# USB.net
KiCad netlist of a schematic drawn in Altium Designer
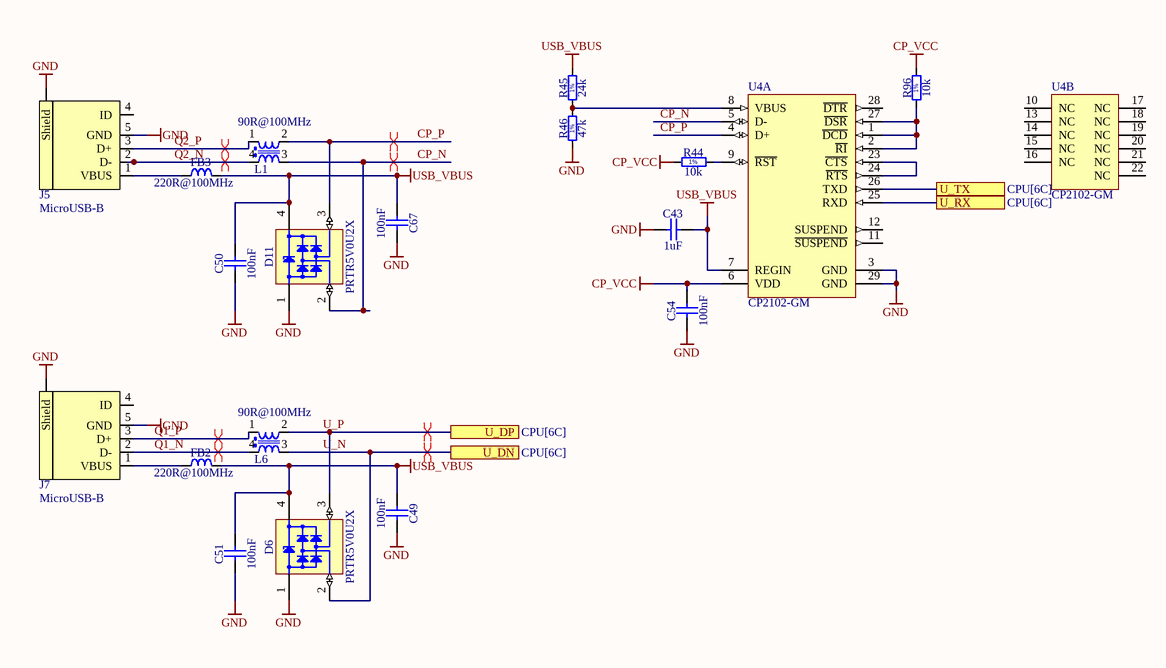
[diagram p0: USB.SchDoc]

(export (version "E")
  (design (tool "Eeschema 10.0.6"))
  (components
    (comp (ref "C43")
      (value "1uF")
      (footprint "CAPC1005X55N")
      (description "Non-polarised capacitor")
      (fields
        (field (name "PART NUMBER") "CC0402_1UF_16V_10%_X5R")
        (field (name "VOLTAGE") "16V")
        (field (name "AUTHOR") "CERN DEM JLC")
      )
      (libsource (lib "Capacitors") (part "Capacitor - non polarized"))
    )
    (comp (ref "C49")
      (value "100nF")
      (footprint "CAPC1005X55N")
      (description "Non-polarised capacitor")
      (fields
        (field (name "PART NUMBER") "CC0402_100NF_16V_10%_X5R")
        (field (name "VOLTAGE") "16V")
        (field (name "AUTHOR") "CERN DEM JLC")
      )
      (libsource (lib "Capacitors") (part "Capacitor - non polarized"))
    )
    (comp (ref "C50")
      (value "100nF")
      (footprint "CAPC1005X55N")
      (description "Non-polarised capacitor")
      (fields
        (field (name "PART NUMBER") "CC0402_100NF_16V_10%_X5R")
        (field (name "VOLTAGE") "16V")
        (field (name "AUTHOR") "CERN DEM JLC")
      )
      (libsource (lib "Capacitors") (part "Capacitor - non polarized"))
    )
    (comp (ref "C51")
      (value "100nF")
      (footprint "CAPC1005X55N")
      (description "Non-polarised capacitor")
      (fields
        (field (name "PART NUMBER") "CC0402_100NF_16V_10%_X5R")
        (field (name "VOLTAGE") "16V")
        (field (name "AUTHOR") "CERN DEM JLC")
      )
      (libsource (lib "Capacitors") (part "Capacitor - non polarized"))
    )
    (comp (ref "C54")
      (value "100nF")
      (footprint "CAPC1005X55N")
      (description "Non-polarised capacitor")
      (fields
        (field (name "PART NUMBER") "CC0402_100NF_16V_10%_X5R")
        (field (name "VOLTAGE") "16V")
        (field (name "AUTHOR") "CERN DEM JLC")
      )
      (libsource (lib "Capacitors") (part "Capacitor - non polarized"))
    )
    (comp (ref "C67")
      (value "100nF")
      (footprint "CAPC1005X55N")
      (description "Non-polarised capacitor")
      (fields
        (field (name "PART NUMBER") "CC0402_100NF_16V_10%_X5R")
        (field (name "VOLTAGE") "16V")
        (field (name "AUTHOR") "CERN DEM JLC")
      )
      (libsource (lib "Capacitors") (part "Capacitor - non polarized"))
    )
    (comp (ref "D6")
      (value "PRTR5V0U2X")
      (footprint "SOT190P230X110-4N")
      (description "Ultra Low Capacitance Double Rail-to-Rail ESD Protection Diode")
      (fields
        (field (name "VOLTAGE") "5.5V")
        (field (name "MANUFACTURER") "NXP SEMICONDUCTORS")
        (field (name "AUTHOR") "CERN DEM JLC")
      )
      (libsource (lib "ICs And Semiconductors") (part "PRTR5V0U2X"))
    )
    (comp (ref "D11")
      (value "PRTR5V0U2X")
      (footprint "SOT190P230X110-4N")
      (description "Ultra Low Capacitance Double Rail-to-Rail ESD Protection Diode")
      (fields
        (field (name "VOLTAGE") "5.5V")
        (field (name "MANUFACTURER") "NXP SEMICONDUCTORS")
        (field (name "AUTHOR") "CERN DEM JLC")
      )
      (libsource (lib "ICs And Semiconductors") (part "PRTR5V0U2X"))
    )
    (comp (ref "FB2")
      (value "220R@100MHz")
      (footprint "INDC2012X105N")
      (description "Inductor")
      (fields
        (field (name "PART NUMBER") "IND0805_MURATA_BLM21PG221SN1D")
        (field (name "POWER") "2A")
        (field (name "AUTHOR") "CERN DEM JLC")
      )
      (libsource (lib "Inductors & Transformers") (part "Inductor"))
    )
    (comp (ref "FB3")
      (value "220R@100MHz")
      (footprint "INDC2012X105N")
      (description "Inductor")
      (fields
        (field (name "PART NUMBER") "IND0805_MURATA_BLM21PG221SN1D")
        (field (name "POWER") "2A")
        (field (name "AUTHOR") "CERN DEM JLC")
      )
      (libsource (lib "Inductors & Transformers") (part "Inductor"))
    )
    (comp (ref "J5")
      (value "MicroUSB-B")
      (footprint "USB-Micro-B-RA-SMD-PiP")
      (description "MicroUSB-B-SMT")
      (fields
        (field (name "PART NUMBER") "USB-Micro-B-RA-SMD-PiP")
        (field (name "MANUFACTURER") "Allen Creations Corp.")
        (field (name "PUBLISHER") "Nordic Semiconductor")
      )
      (libsource (lib "Nordic Passive DB") (part "MiniUSB-AB-SMT"))
    )
    (comp (ref "J7")
      (value "MicroUSB-B")
      (footprint "USB-Micro-B-RA-SMD-PiP")
      (description "MicroUSB-B-SMT")
      (fields
        (field (name "PART NUMBER") "USB-Micro-B-RA-SMD-PiP")
        (field (name "MANUFACTURER") "Allen Creations Corp.")
        (field (name "PUBLISHER") "Nordic Semiconductor")
      )
      (libsource (lib "Nordic Passive DB") (part "MiniUSB-AB-SMT"))
    )
    (comp (ref "L1")
      (value "90R@100MHz")
      (footprint "IND_MURATA_DLW21S")
      (description "Inductor Common Mode")
      (fields
        (field (name "PART NUMBER") "IND_MURATA_DLW21SN900SQ2L")
        (field (name "POWER") "330mA")
        (field (name "AUTHOR") "CERN DEM JLC")
      )
      (libsource (lib "Inductors & Transformers") (part "Inductor Common Mode 1Dot-2 4Dot-3"))
    )
    (comp (ref "L6")
      (value "90R@100MHz")
      (footprint "IND_MURATA_DLW21S")
      (description "Inductor Common Mode")
      (fields
        (field (name "PART NUMBER") "IND_MURATA_DLW21SN900SQ2L")
        (field (name "POWER") "330mA")
        (field (name "AUTHOR") "CERN DEM JLC")
      )
      (libsource (lib "Inductors & Transformers") (part "Inductor Common Mode 1Dot-2 4Dot-3"))
    )
    (comp (ref "R44")
      (value "10k")
      (footprint "RESC1005X40N")
      (description "Resistor - 1%")
      (fields
        (field (name "PART NUMBER") "R0402_10K_1%_0.0625W_100PPM")
        (field (name "POWER") "0.0625W")
        (field (name "AUTHOR") "CERN DEM JLC")
      )
      (libsource (lib "Resistors") (part "Resistor - 1%"))
    )
    (comp (ref "R45")
      (value "24k")
      (footprint "RESC1005X40N")
      (description "Resistor - 1%")
      (fields
        (field (name "PART NUMBER") "R0402_24K_1%_0.0625W_100PPM")
        (field (name "POWER") "0.0625W")
        (field (name "AUTHOR") "CERN DEM JLC")
      )
      (libsource (lib "Resistors") (part "Resistor - 1%"))
    )
    (comp (ref "R46")
      (value "47k")
      (footprint "RESC1005X40N")
      (description "Resistor - 1%")
      (fields
        (field (name "PART NUMBER") "R0402_47K_1%_0.0625W_100PPM")
        (field (name "POWER") "0.0625W")
        (field (name "AUTHOR") "CERN DEM JLC")
      )
      (libsource (lib "Resistors") (part "Resistor - 1%"))
    )
    (comp (ref "R96")
      (value "10k")
      (footprint "RESC1005X40N")
      (description "Resistor - 1%")
      (fields
        (field (name "PART NUMBER") "R0402_10K_1%_0.0625W_100PPM")
        (field (name "POWER") "0.0625W")
        (field (name "AUTHOR") "CERN DEM JLC")
      )
      (libsource (lib "Resistors") (part "Resistor - 1%"))
    )
    (comp (ref "U4")
      (value "CP2102-GM")
      (footprint "SLAB-QFN-28-3125x3125TP_N")
      (description "Single-Chip USB to UART Bridge, 1024 Bytes EEPROM, -40 to 85 degC, 28-pin QFN, Tube")
      (fields (field (name "MANUFACTURER") "Silicon Labs"))
      (libsource (lib "Silicon Labs Interface") (part "CP2102-GM"))
    )
  )
  (nets
    (net (code "1") (name "/CP_N") (class "Default")
      (node (ref "D11") (pin "2") (pinfunction "I/O1_2") (pintype "bidirectional"))
      (node (ref "L1") (pin "3") (pinfunction "3_3") (pintype "passive"))
      (node (ref "U4") (pin "5") (pinfunction "D-_5") (pintype "bidirectional"))
    )
    (net (code "2") (name "/CP_P") (class "Default")
      (node (ref "D11") (pin "3") (pinfunction "I/O2_3") (pintype "bidirectional"))
      (node (ref "L1") (pin "2") (pinfunction "2_2") (pintype "passive"))
      (node (ref "U4") (pin "4") (pinfunction "D+_4") (pintype "bidirectional"))
    )
    (net (code "3") (name "/Q1_N") (class "Default")
      (node (ref "J7") (pin "2") (pinfunction "D-_2") (pintype "passive"))
      (node (ref "L6") (pin "4") (pinfunction "4_4") (pintype "passive"))
    )
    (net (code "4") (name "/Q1_P") (class "Default")
      (node (ref "J7") (pin "3") (pinfunction "D+_3") (pintype "passive"))
      (node (ref "L6") (pin "1") (pinfunction "1_1") (pintype "passive"))
    )
    (net (code "5") (name "/Q2_N") (class "Default")
      (node (ref "J5") (pin "2") (pinfunction "D-_2") (pintype "passive"))
      (node (ref "L1") (pin "4") (pinfunction "4_4") (pintype "passive"))
    )
    (net (code "6") (name "/Q2_P") (class "Default")
      (node (ref "J5") (pin "3") (pinfunction "D+_3") (pintype "passive"))
      (node (ref "L1") (pin "1") (pinfunction "1_1") (pintype "passive"))
    )
    (net (code "7") (name "/U_N") (class "Default")
      (node (ref "D6") (pin "2") (pinfunction "I/O1_2") (pintype "bidirectional"))
      (node (ref "L6") (pin "3") (pinfunction "3_3") (pintype "passive"))
    )
    (net (code "8") (name "/U_P") (class "Default")
      (node (ref "D6") (pin "3") (pinfunction "I/O2_3") (pintype "bidirectional"))
      (node (ref "L6") (pin "2") (pinfunction "2_2") (pintype "passive"))
    )
    (net (code "9") (name "/U_RX") (class "Default")
      (node (ref "U4") (pin "25") (pinfunction "RXD_25") (pintype "input"))
    )
    (net (code "10") (name "/U_TX") (class "Default")
      (node (ref "U4") (pin "26") (pinfunction "TXD_26") (pintype "output"))
    )
    (net (code "11") (name "CP_VCC") (class "Default")
      (node (ref "C54") (pin "2") (pinfunction "2_2") (pintype "passive"))
      (node (ref "R44") (pin "1") (pinfunction "1_1") (pintype "passive"))
      (node (ref "R96") (pin "2") (pinfunction "2_2") (pintype "passive"))
      (node (ref "U4") (pin "6") (pinfunction "VDD_6") (pintype "power_in"))
    )
    (net (code "12") (name "GND") (class "Default")
      (node (ref "C43") (pin "1") (pinfunction "1_1") (pintype "passive"))
      (node (ref "C49") (pin "2") (pinfunction "2_2") (pintype "passive"))
      (node (ref "C50") (pin "1") (pinfunction "1_1") (pintype "passive"))
      (node (ref "C51") (pin "1") (pinfunction "1_1") (pintype "passive"))
      (node (ref "C54") (pin "1") (pinfunction "1_1") (pintype "passive"))
      (node (ref "C67") (pin "2") (pinfunction "2_2") (pintype "passive"))
      (node (ref "D11") (pin "1") (pinfunction "GND_1") (pintype "power_in"))
      (node (ref "D6") (pin "1") (pinfunction "GND_1") (pintype "power_in"))
      (node (ref "J5") (pin "5") (pinfunction "GND_5") (pintype "power_in"))
      (node (ref "J5") (pin "6") (pinfunction "Shield_6") (pintype "power_in"))
      (node (ref "J7") (pin "5") (pinfunction "GND_5") (pintype "power_in"))
      (node (ref "J7") (pin "6") (pinfunction "Shield_6") (pintype "power_in"))
      (node (ref "R46") (pin "1") (pinfunction "1_1") (pintype "passive"))
      (node (ref "U4") (pin "29") (pinfunction "GND_29") (pintype "power_in"))
      (node (ref "U4") (pin "3") (pinfunction "GND_3") (pintype "power_in"))
    )
    (net (code "13") (name "Net-(J5-VBUS)") (class "Default")
      (node (ref "FB3") (pin "1") (pinfunction "1_1") (pintype "passive"))
      (node (ref "J5") (pin "1") (pinfunction "VBUS_1") (pintype "power_in"))
    )
    (net (code "14") (name "Net-(J7-VBUS)") (class "Default")
      (node (ref "FB2") (pin "1") (pinfunction "1_1") (pintype "passive"))
      (node (ref "J7") (pin "1") (pinfunction "VBUS_1") (pintype "power_in"))
    )
    (net (code "15") (name "Net-(U4A-VBUS)") (class "Default")
      (node (ref "R45") (pin "1") (pinfunction "1_1") (pintype "passive"))
      (node (ref "R46") (pin "2") (pinfunction "2_2") (pintype "passive"))
      (node (ref "U4") (pin "8") (pinfunction "VBUS_8") (pintype "input"))
    )
    (net (code "16") (name "Net-(U4A-~{CTS})") (class "Default")
      (node (ref "U4") (pin "23") (pinfunction "~{CTS}_23") (pintype "input"))
      (node (ref "U4") (pin "24") (pinfunction "~{RTS}_24") (pintype "output"))
    )
    (net (code "17") (name "Net-(U4A-~{DCD})") (class "Default")
      (node (ref "R96") (pin "1") (pinfunction "1_1") (pintype "passive"))
      (node (ref "U4") (pin "1") (pinfunction "~{DCD}_1") (pintype "input"))
      (node (ref "U4") (pin "2") (pinfunction "~{RI}_2") (pintype "input"))
      (node (ref "U4") (pin "27") (pinfunction "~{DSR}_27") (pintype "input"))
    )
    (net (code "18") (name "Net-(U4A-~{RST})") (class "Default")
      (node (ref "R44") (pin "2") (pinfunction "2_2") (pintype "passive"))
      (node (ref "U4") (pin "9") (pinfunction "~{RST}_9") (pintype "bidirectional"))
    )
    (net (code "19") (name "USB_VBUS") (class "Default")
      (node (ref "C43") (pin "2") (pinfunction "2_2") (pintype "passive"))
      (node (ref "C49") (pin "1") (pinfunction "1_1") (pintype "passive"))
      (node (ref "C50") (pin "2") (pinfunction "2_2") (pintype "passive"))
      (node (ref "C51") (pin "2") (pinfunction "2_2") (pintype "passive"))
      (node (ref "C67") (pin "1") (pinfunction "1_1") (pintype "passive"))
      (node (ref "D11") (pin "4") (pinfunction "VCC_4") (pintype "power_in"))
      (node (ref "D6") (pin "4") (pinfunction "VCC_4") (pintype "power_in"))
      (node (ref "FB2") (pin "2") (pinfunction "2_2") (pintype "passive"))
      (node (ref "FB3") (pin "2") (pinfunction "2_2") (pintype "passive"))
      (node (ref "R45") (pin "2") (pinfunction "2_2") (pintype "passive"))
      (node (ref "U4") (pin "7") (pinfunction "REGIN_7") (pintype "power_in"))
    )
    (net (code "20") (name "unconnected-(J5-ID-Pad4)") (class "Default")
      (node (ref "J5") (pin "4") (pinfunction "ID_4") (pintype "passive"))
    )
    (net (code "21") (name "unconnected-(J7-ID-Pad4)") (class "Default")
      (node (ref "J7") (pin "4") (pinfunction "ID_4") (pintype "passive"))
    )
    (net (code "22") (name "unconnected-(U4A-SUSPEND-Pad12)") (class "Default")
      (node (ref "U4") (pin "12") (pinfunction "SUSPEND_12") (pintype "output"))
    )
    (net (code "23") (name "unconnected-(U4A-~{DTR}-Pad28)") (class "Default")
      (node (ref "U4") (pin "28") (pinfunction "~{DTR}_28") (pintype "output"))
    )
    (net (code "24") (name "unconnected-(U4A-~{SUSPEND}-Pad11)") (class "Default")
      (node (ref "U4") (pin "11") (pinfunction "~{SUSPEND}_11") (pintype "output"))
    )
    (net (code "25") (name "unconnected-(U4B-NC-Pad10)") (class "Default")
      (node (ref "U4") (pin "10") (pinfunction "NC_10") (pintype "passive"))
    )
    (net (code "26") (name "unconnected-(U4B-NC-Pad13)") (class "Default")
      (node (ref "U4") (pin "13") (pinfunction "NC_13") (pintype "passive"))
    )
    (net (code "27") (name "unconnected-(U4B-NC-Pad14)") (class "Default")
      (node (ref "U4") (pin "14") (pinfunction "NC_14") (pintype "passive"))
    )
    (net (code "28") (name "unconnected-(U4B-NC-Pad15)") (class "Default")
      (node (ref "U4") (pin "15") (pinfunction "NC_15") (pintype "passive"))
    )
    (net (code "29") (name "unconnected-(U4B-NC-Pad16)") (class "Default")
      (node (ref "U4") (pin "16") (pinfunction "NC_16") (pintype "passive"))
    )
    (net (code "30") (name "unconnected-(U4B-NC-Pad17)") (class "Default")
      (node (ref "U4") (pin "17") (pinfunction "NC_17") (pintype "passive"))
    )
    (net (code "31") (name "unconnected-(U4B-NC-Pad18)") (class "Default")
      (node (ref "U4") (pin "18") (pinfunction "NC_18") (pintype "passive"))
    )
    (net (code "32") (name "unconnected-(U4B-NC-Pad19)") (class "Default")
      (node (ref "U4") (pin "19") (pinfunction "NC_19") (pintype "passive"))
    )
    (net (code "33") (name "unconnected-(U4B-NC-Pad20)") (class "Default")
      (node (ref "U4") (pin "20") (pinfunction "NC_20") (pintype "passive"))
    )
    (net (code "34") (name "unconnected-(U4B-NC-Pad21)") (class "Default")
      (node (ref "U4") (pin "21") (pinfunction "NC_21") (pintype "passive"))
    )
    (net (code "35") (name "unconnected-(U4B-NC-Pad22)") (class "Default")
      (node (ref "U4") (pin "22") (pinfunction "NC_22") (pintype "passive"))
    )
  )
)
